# design.net
KiCad netlist of a schematic drawn in Altium Designer
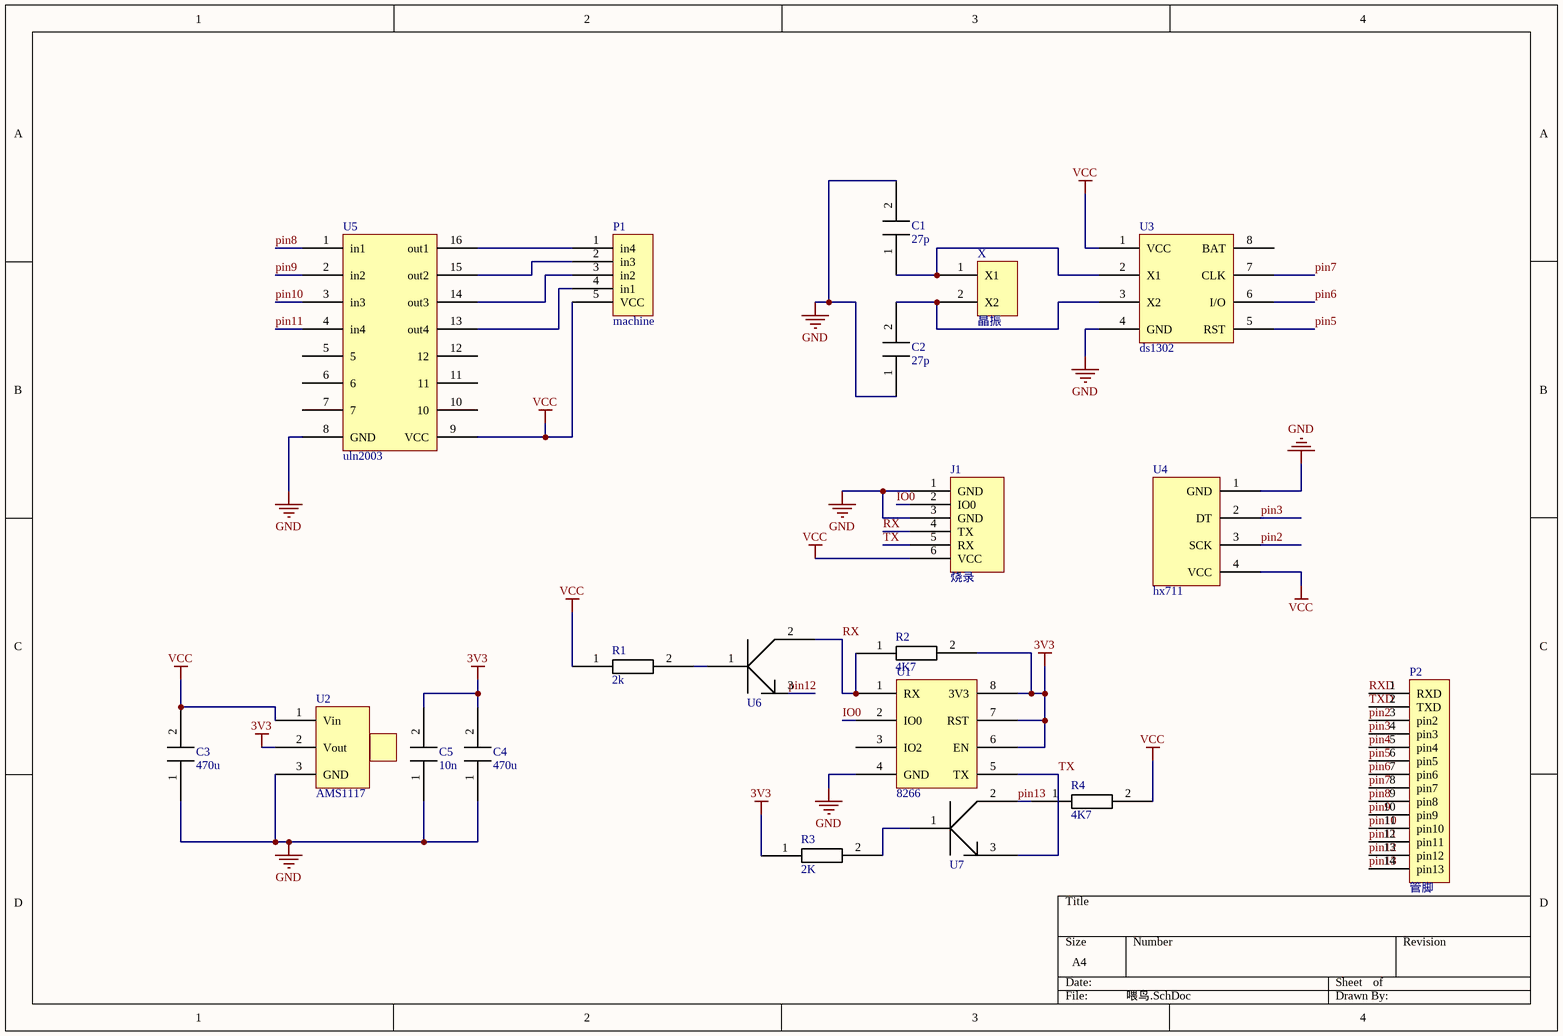
[diagram p0: 喂鸟.SchDoc]

(export (version "E")
  (design (tool "Eeschema 10.0.6"))
  (components
    (comp (ref "C1") (value "27p") (footprint "C") (libsource (lib "喂鸟") (part "C")))
    (comp (ref "C2") (value "27p") (footprint "C") (libsource (lib "喂鸟") (part "C")))
    (comp (ref "C3") (value "470u") (footprint "0805") (libsource (lib "喂鸟") (part "C")))
    (comp (ref "C4") (value "470u") (footprint "0805") (libsource (lib "喂鸟") (part "C")))
    (comp (ref "C5") (value "10n") (footprint "0805") (libsource (lib "喂鸟") (part "C")))
    (comp (ref "J1") (value "烧录") (libsource (lib "喂鸟") (part "烧录")))
    (comp (ref "P1") (value "machine") (footprint "machine") (libsource (lib "喂鸟") (part "machine")))
    (comp (ref "P2") (value "管脚") (footprint "接口") (libsource (lib "喂鸟") (part "管脚")))
    (comp (ref "R1") (value "2k") (footprint "R") (libsource (lib "喂鸟") (part "R")))
    (comp (ref "R2") (value "4K7") (footprint "R") (libsource (lib "喂鸟") (part "R")))
    (comp (ref "R3") (value "2K") (footprint "R") (libsource (lib "喂鸟") (part "R")))
    (comp (ref "R4") (value "4K7") (footprint "R") (libsource (lib "喂鸟") (part "R")))
    (comp (ref "U1") (value "8266") (footprint "8266") (libsource (lib "喂鸟") (part "8266")))
    (comp (ref "U2") (value "AMS1117") (footprint "SOT223") (libsource (lib "喂鸟") (part "AMS1117")))
    (comp (ref "U3") (value "ds1302") (footprint "DIP8") (libsource (lib "喂鸟") (part "ds1302")))
    (comp (ref "U4") (value "hx711") (footprint "HX711") (libsource (lib "喂鸟") (part "hx711")))
    (comp (ref "U5") (value "uln2003") (footprint "DIP16") (libsource (lib "喂鸟") (part "uln2003")))
    (comp (ref "U6") (value "8050") (footprint "TO_92") (libsource (lib "喂鸟") (part "8050")))
    (comp (ref "U7") (value "8050") (footprint "TO_92") (libsource (lib "喂鸟") (part "8050")))
    (comp (ref "X") (value "晶振") (footprint "晶振") (libsource (lib "喂鸟") (part "晶振")))
  )
  (nets
    (net (code "1") (name "/IO0") (class "Default")
      (node (ref "J1") (pin "2") (pinfunction "IO0_2") (pintype "passive"))
      (node (ref "U1") (pin "2") (pinfunction "IO0_2") (pintype "passive"))
    )
    (net (code "2") (name "/RX") (class "Default")
      (node (ref "J1") (pin "4") (pinfunction "TX_4") (pintype "passive"))
      (node (ref "R2") (pin "1") (pinfunction "4_1") (pintype "passive"))
      (node (ref "U1") (pin "1") (pinfunction "RX_1") (pintype "passive"))
      (node (ref "U6") (pin "2") (pinfunction "2_2") (pintype "passive"))
    )
    (net (code "3") (name "/RXD") (class "Default")
      (node (ref "P2") (pin "1") (pinfunction "RXD_1") (pintype "passive"))
    )
    (net (code "4") (name "/TX") (class "Default")
      (node (ref "J1") (pin "5") (pinfunction "RX_5") (pintype "passive"))
      (node (ref "U1") (pin "5") (pinfunction "TX_5") (pintype "passive"))
      (node (ref "U7") (pin "3") (pinfunction "3_3") (pintype "passive"))
    )
    (net (code "5") (name "/TXD") (class "Default")
      (node (ref "P2") (pin "2") (pinfunction "TXD_2") (pintype "passive"))
    )
    (net (code "6") (name "/pin2") (class "Default")
      (node (ref "P2") (pin "3") (pinfunction "pin2_3") (pintype "passive"))
      (node (ref "U4") (pin "3") (pinfunction "SCK_3") (pintype "passive"))
    )
    (net (code "7") (name "/pin3") (class "Default")
      (node (ref "P2") (pin "4") (pinfunction "pin3_4") (pintype "passive"))
      (node (ref "U4") (pin "2") (pinfunction "DT_2") (pintype "passive"))
    )
    (net (code "8") (name "/pin4") (class "Default")
      (node (ref "P2") (pin "5") (pinfunction "pin4_5") (pintype "passive"))
    )
    (net (code "9") (name "/pin5") (class "Default")
      (node (ref "P2") (pin "6") (pinfunction "pin5_6") (pintype "passive"))
      (node (ref "U3") (pin "5") (pinfunction "RST_5") (pintype "passive"))
    )
    (net (code "10") (name "/pin6") (class "Default")
      (node (ref "P2") (pin "7") (pinfunction "pin6_7") (pintype "passive"))
      (node (ref "U3") (pin "6") (pinfunction "I/O_6") (pintype "passive"))
    )
    (net (code "11") (name "/pin7") (class "Default")
      (node (ref "P2") (pin "8") (pinfunction "pin7_8") (pintype "passive"))
      (node (ref "U3") (pin "7") (pinfunction "CLK_7") (pintype "passive"))
    )
    (net (code "12") (name "/pin8") (class "Default")
      (node (ref "P2") (pin "9") (pinfunction "pin8_9") (pintype "passive"))
      (node (ref "U5") (pin "1") (pinfunction "in1_1") (pintype "passive"))
    )
    (net (code "13") (name "/pin9") (class "Default")
      (node (ref "P2") (pin "10") (pinfunction "pin9_10") (pintype "passive"))
      (node (ref "U5") (pin "2") (pinfunction "in2_2") (pintype "passive"))
    )
    (net (code "14") (name "/pin10") (class "Default")
      (node (ref "P2") (pin "11") (pinfunction "pin10_11") (pintype "passive"))
      (node (ref "U5") (pin "3") (pinfunction "in3_3") (pintype "passive"))
    )
    (net (code "15") (name "/pin11") (class "Default")
      (node (ref "P2") (pin "12") (pinfunction "pin11_12") (pintype "passive"))
      (node (ref "U5") (pin "4") (pinfunction "in4_4") (pintype "passive"))
    )
    (net (code "16") (name "/pin12") (class "Default")
      (node (ref "P2") (pin "13") (pinfunction "pin12_13") (pintype "passive"))
      (node (ref "U6") (pin "3") (pinfunction "3_3") (pintype "passive"))
    )
    (net (code "17") (name "/pin13") (class "Default")
      (node (ref "P2") (pin "14") (pinfunction "pin13_14") (pintype "passive"))
      (node (ref "R4") (pin "1") (pinfunction "4_1") (pintype "passive"))
      (node (ref "U7") (pin "2") (pinfunction "2_2") (pintype "passive"))
    )
    (net (code "18") (name "3V3") (class "Default")
      (node (ref "C4") (pin "2") (pinfunction "2_2") (pintype "passive"))
      (node (ref "C5") (pin "2") (pinfunction "2_2") (pintype "passive"))
      (node (ref "R2") (pin "2") (pinfunction "4_2") (pintype "passive"))
      (node (ref "R3") (pin "1") (pinfunction "4_1") (pintype "passive"))
      (node (ref "U1") (pin "6") (pinfunction "EN_6") (pintype "passive"))
      (node (ref "U1") (pin "7") (pinfunction "RST_7") (pintype "passive"))
      (node (ref "U1") (pin "8") (pinfunction "3V3_8") (pintype "passive"))
      (node (ref "U2") (pin "2") (pinfunction "Vout_2") (pintype "passive"))
    )
    (net (code "19") (name "GND") (class "Default")
      (node (ref "C1") (pin "2") (pinfunction "2_2") (pintype "passive"))
      (node (ref "C2") (pin "1") (pinfunction "3_1") (pintype "passive"))
      (node (ref "C3") (pin "1") (pinfunction "3_1") (pintype "passive"))
      (node (ref "C4") (pin "1") (pinfunction "3_1") (pintype "passive"))
      (node (ref "C5") (pin "1") (pinfunction "3_1") (pintype "passive"))
      (node (ref "J1") (pin "1") (pinfunction "GND_1") (pintype "passive"))
      (node (ref "J1") (pin "3") (pinfunction "GND_3") (pintype "passive"))
      (node (ref "U1") (pin "4") (pinfunction "GND_4") (pintype "passive"))
      (node (ref "U2") (pin "3") (pinfunction "GND_3") (pintype "passive"))
      (node (ref "U3") (pin "4") (pinfunction "GND_4") (pintype "passive"))
      (node (ref "U4") (pin "1") (pinfunction "GND_1") (pintype "passive"))
      (node (ref "U5") (pin "8") (pinfunction "GND_8") (pintype "passive"))
    )
    (net (code "20") (name "Net-(C1-3)") (class "Default")
      (node (ref "C1") (pin "1") (pinfunction "3_1") (pintype "passive"))
      (node (ref "U3") (pin "2") (pinfunction "X1_2") (pintype "passive"))
      (node (ref "X") (pin "1") (pinfunction "X1_1") (pintype "passive"))
    )
    (net (code "21") (name "Net-(P1-in1)") (class "Default")
      (node (ref "P1") (pin "4") (pinfunction "in1_4") (pintype "passive"))
      (node (ref "U5") (pin "13") (pinfunction "out4_13") (pintype "passive"))
    )
    (net (code "22") (name "Net-(P1-in2)") (class "Default")
      (node (ref "P1") (pin "3") (pinfunction "in2_3") (pintype "passive"))
      (node (ref "U5") (pin "14") (pinfunction "out3_14") (pintype "passive"))
    )
    (net (code "23") (name "Net-(P1-in3)") (class "Default")
      (node (ref "P1") (pin "2") (pinfunction "in3_2") (pintype "passive"))
      (node (ref "U5") (pin "15") (pinfunction "out2_15") (pintype "passive"))
    )
    (net (code "24") (name "Net-(P1-in4)") (class "Default")
      (node (ref "P1") (pin "1") (pinfunction "in4_1") (pintype "passive"))
      (node (ref "U5") (pin "16") (pinfunction "out1_16") (pintype "passive"))
    )
    (net (code "25") (name "Net-(U3-X2)") (class "Default")
      (node (ref "C2") (pin "2") (pinfunction "2_2") (pintype "passive"))
      (node (ref "U3") (pin "3") (pinfunction "X2_3") (pintype "passive"))
      (node (ref "X") (pin "2") (pinfunction "X2_2") (pintype "passive"))
    )
    (net (code "26") (name "Net-(U6-6)") (class "Default")
      (node (ref "R1") (pin "2") (pinfunction "4_2") (pintype "passive"))
      (node (ref "U6") (pin "1") (pinfunction "6_1") (pintype "passive"))
    )
    (net (code "27") (name "Net-(U7-6)") (class "Default")
      (node (ref "R3") (pin "2") (pinfunction "4_2") (pintype "passive"))
      (node (ref "U7") (pin "1") (pinfunction "6_1") (pintype "passive"))
    )
    (net (code "28") (name "VCC") (class "Default")
      (node (ref "C3") (pin "2") (pinfunction "2_2") (pintype "passive"))
      (node (ref "J1") (pin "6") (pinfunction "VCC_6") (pintype "passive"))
      (node (ref "P1") (pin "5") (pinfunction "VCC_5") (pintype "passive"))
      (node (ref "R1") (pin "1") (pinfunction "4_1") (pintype "passive"))
      (node (ref "R4") (pin "2") (pinfunction "4_2") (pintype "passive"))
      (node (ref "U2") (pin "1") (pinfunction "Vin_1") (pintype "passive"))
      (node (ref "U3") (pin "1") (pinfunction "VCC_1") (pintype "passive"))
      (node (ref "U4") (pin "4") (pinfunction "VCC_4") (pintype "passive"))
      (node (ref "U5") (pin "9") (pinfunction "VCC_9") (pintype "passive"))
    )
    (net (code "29") (name "unconnected-(U1-IO2-Pad3)") (class "Default")
      (node (ref "U1") (pin "3") (pinfunction "IO2_3") (pintype "passive"))
    )
    (net (code "30") (name "unconnected-(U3-BAT-Pad8)") (class "Default")
      (node (ref "U3") (pin "8") (pinfunction "BAT_8") (pintype "passive"))
    )
    (net (code "31") (name "unconnected-(U5-Pad5)") (class "Default")
      (node (ref "U5") (pin "5") (pinfunction "5_5") (pintype "passive"))
    )
    (net (code "32") (name "unconnected-(U5-Pad6)") (class "Default")
      (node (ref "U5") (pin "6") (pinfunction "6_6") (pintype "passive"))
    )
    (net (code "33") (name "unconnected-(U5-Pad7)") (class "Default")
      (node (ref "U5") (pin "7") (pinfunction "7_7") (pintype "passive"))
    )
    (net (code "34") (name "unconnected-(U5-Pad10)") (class "Default")
      (node (ref "U5") (pin "10") (pinfunction "10_10") (pintype "passive"))
    )
    (net (code "35") (name "unconnected-(U5-Pad11)") (class "Default")
      (node (ref "U5") (pin "11") (pinfunction "11_11") (pintype "passive"))
    )
    (net (code "36") (name "unconnected-(U5-Pad12)") (class "Default")
      (node (ref "U5") (pin "12") (pinfunction "12_12") (pintype "passive"))
    )
  )
)
